# Driver.net
KiCad netlist of a schematic drawn in Altium Designer
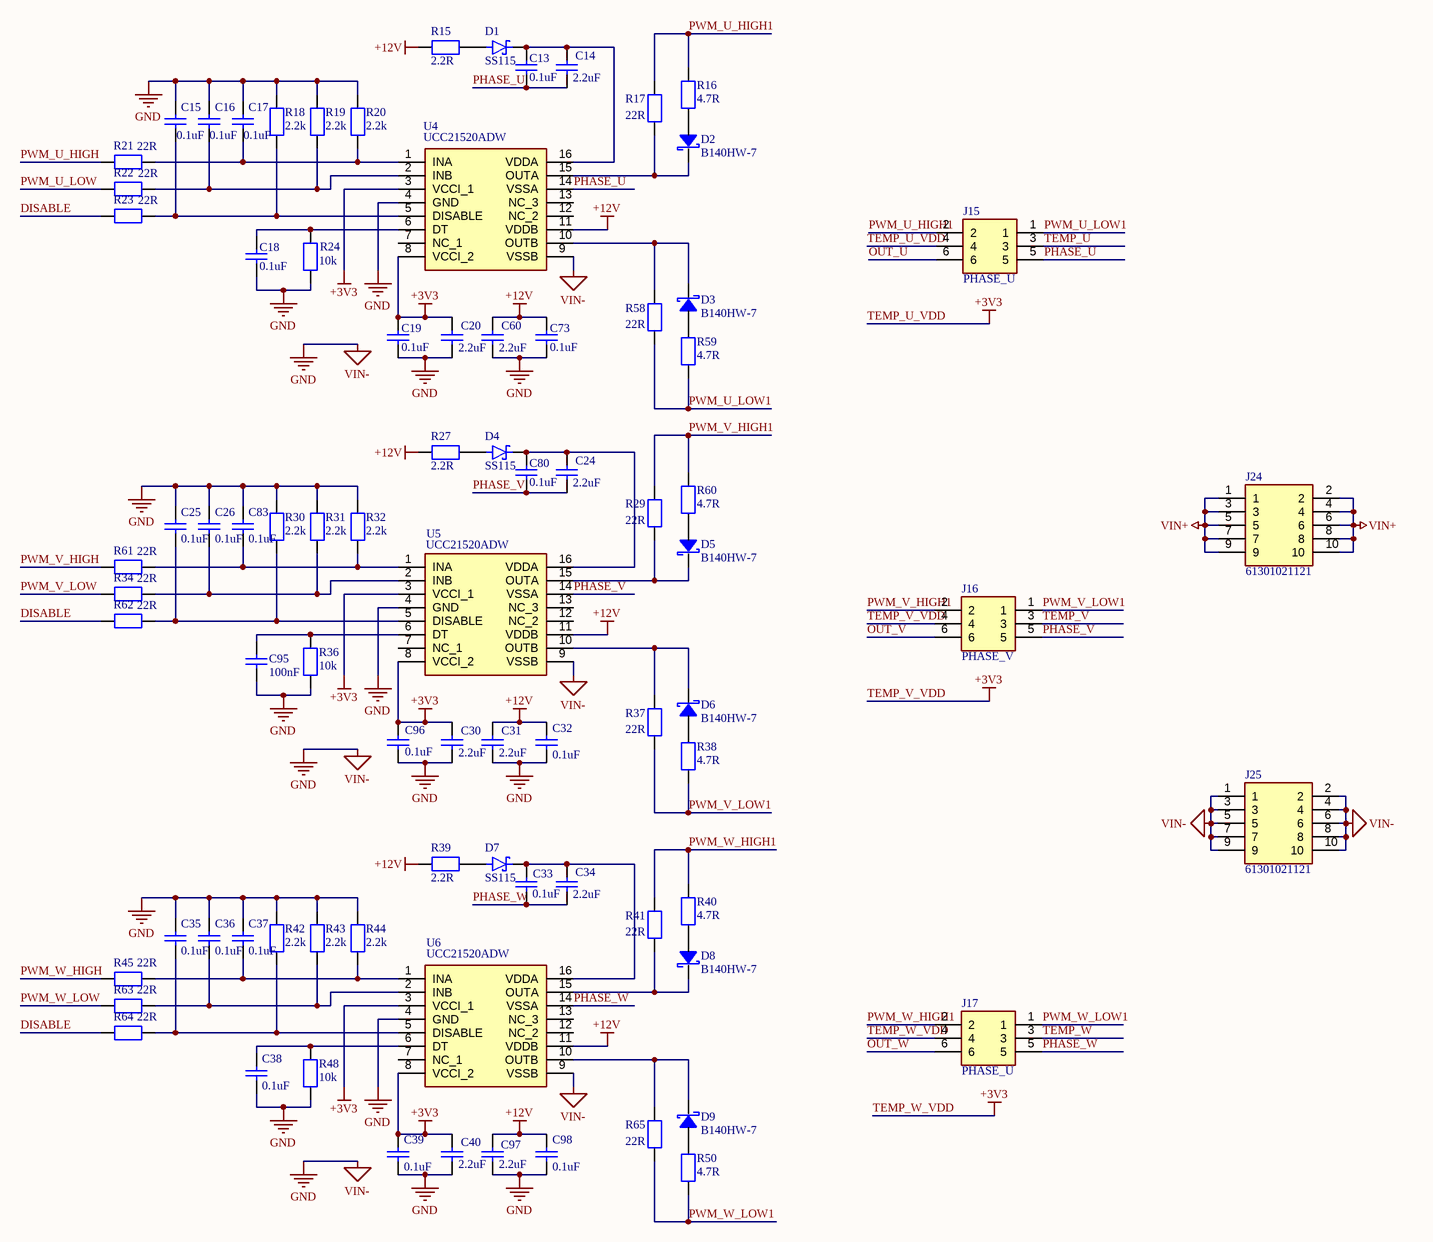
[diagram p0: Driver.SchDoc]

(export (version "E")
  (design (tool "Eeschema 10.0.6"))
  (components
    (comp (ref "C13")
      (value "0.1uF")
      (footprint "C0603")
      (description "Multilayer Ceramic Capacitors MLCC - SMD/SMT 50 V 0.1uF X7R 0603 10%")
      (fields
        (field (name "MANUFACTURER") "Yageo")
        (field (name "MANUFACTURER PART NUMBER") "CC0603KRX7R9BB104")
      )
      (libsource (lib "VESC_MotorController") (part "Cap 100nF ± 10% 50V"))
    )
    (comp (ref "C14")
      (value "2.2uF")
      (footprint "C0805")
      (description "Multilayer Ceramic Capacitors MLCC - SMD/SMT 50 V 2.2uF X7R 0805 10%")
      (fields
        (field (name "MANUFACTURER") "Yageo")
        (field (name "MANUFACTURER PART NUMBER") "CC0805KKX7R9BB225")
      )
      (libsource (lib "VESC_MotorController") (part "Cap 2.2uF ± 10% 50V"))
    )
    (comp (ref "C15")
      (value "0.1uF")
      (footprint "C0603")
      (description "Multilayer Ceramic Capacitors MLCC - SMD/SMT 50 V 0.1uF X7R 0603 10%")
      (fields
        (field (name "MANUFACTURER") "Yageo")
        (field (name "MANUFACTURER PART NUMBER") "CC0603KRX7R9BB104")
      )
      (libsource (lib "VESC_MotorController") (part "Cap 100nF ± 10% 50V"))
    )
    (comp (ref "C16")
      (value "0.1uF")
      (footprint "C0603")
      (description "Multilayer Ceramic Capacitors MLCC - SMD/SMT 50 V 0.1uF X7R 0603 10%")
      (fields
        (field (name "MANUFACTURER") "Yageo")
        (field (name "MANUFACTURER PART NUMBER") "CC0603KRX7R9BB104")
      )
      (libsource (lib "VESC_MotorController") (part "Cap 100nF ± 10% 50V"))
    )
    (comp (ref "C17")
      (value "0.1uF")
      (footprint "C0603")
      (description "Multilayer Ceramic Capacitors MLCC - SMD/SMT 50 V 0.1uF X7R 0603 10%")
      (fields
        (field (name "MANUFACTURER") "Yageo")
        (field (name "MANUFACTURER PART NUMBER") "CC0603KRX7R9BB104")
      )
      (libsource (lib "VESC_MotorController") (part "Cap 100nF ± 10% 50V"))
    )
    (comp (ref "C18")
      (value "0.1uF")
      (footprint "C0603")
      (description "Multilayer Ceramic Capacitors MLCC - SMD/SMT 50 V 0.1uF X7R 0603 10%")
      (fields
        (field (name "MANUFACTURER") "Yageo")
        (field (name "MANUFACTURER PART NUMBER") "CC0603KRX7R9BB104")
      )
      (libsource (lib "VESC_MotorController") (part "Cap 100nF ± 10% 50V"))
    )
    (comp (ref "C19")
      (value "0.1uF")
      (footprint "C0603")
      (description "Multilayer Ceramic Capacitors MLCC - SMD/SMT 50 V 0.1uF X7R 0603 10%")
      (fields
        (field (name "MANUFACTURER") "Yageo")
        (field (name "MANUFACTURER PART NUMBER") "CC0603KRX7R9BB104")
      )
      (libsource (lib "VESC_MotorController") (part "Cap 100nF ± 10% 50V"))
    )
    (comp (ref "C20")
      (value "2.2uF")
      (footprint "C0805")
      (description "Multilayer Ceramic Capacitors MLCC - SMD/SMT 50 V 2.2uF X7R 0805 10%")
      (fields
        (field (name "MANUFACTURER") "Yageo")
        (field (name "MANUFACTURER PART NUMBER") "CC0805KKX7R9BB225")
      )
      (libsource (lib "VESC_MotorController") (part "Cap 2.2uF ± 10% 50V"))
    )
    (comp (ref "C24")
      (value "2.2uF")
      (footprint "C0805")
      (description "Multilayer Ceramic Capacitors MLCC - SMD/SMT 50 V 2.2uF X7R 0805 10%")
      (fields
        (field (name "MANUFACTURER") "Yageo")
        (field (name "MANUFACTURER PART NUMBER") "CC0805KKX7R9BB225")
      )
      (libsource (lib "VESC_MotorController") (part "Cap 2.2uF ± 10% 50V"))
    )
    (comp (ref "C25")
      (value "0.1uF")
      (footprint "C0603")
      (description "Multilayer Ceramic Capacitors MLCC - SMD/SMT 50 V 0.1uF X7R 0603 10%")
      (fields
        (field (name "MANUFACTURER") "Yageo")
        (field (name "MANUFACTURER PART NUMBER") "CC0603KRX7R9BB104")
      )
      (libsource (lib "VESC_MotorController") (part "Cap 100nF ± 10% 50V"))
    )
    (comp (ref "C26")
      (value "0.1uF")
      (footprint "C0603")
      (description "Multilayer Ceramic Capacitors MLCC - SMD/SMT 50 V 0.1uF X7R 0603 10%")
      (fields
        (field (name "MANUFACTURER") "Yageo")
        (field (name "MANUFACTURER PART NUMBER") "CC0603KRX7R9BB104")
      )
      (libsource (lib "VESC_MotorController") (part "Cap 100nF ± 10% 50V"))
    )
    (comp (ref "C30")
      (value "2.2uF")
      (footprint "C0805")
      (description "Multilayer Ceramic Capacitors MLCC - SMD/SMT 50 V 2.2uF X7R 0805 10%")
      (fields
        (field (name "MANUFACTURER") "Yageo")
        (field (name "MANUFACTURER PART NUMBER") "CC0805KKX7R9BB225")
      )
      (libsource (lib "VESC_MotorController") (part "Cap 2.2uF ± 10% 50V"))
    )
    (comp (ref "C31")
      (value "2.2uF")
      (footprint "C0805")
      (description "Multilayer Ceramic Capacitors MLCC - SMD/SMT 50 V 2.2uF X7R 0805 10%")
      (fields
        (field (name "MANUFACTURER") "Yageo")
        (field (name "MANUFACTURER PART NUMBER") "CC0805KKX7R9BB225")
      )
      (libsource (lib "VESC_MotorController") (part "Cap 2.2uF ± 10% 50V"))
    )
    (comp (ref "C32")
      (value "0.1uF")
      (footprint "C0603")
      (description "Multilayer Ceramic Capacitors MLCC - SMD/SMT 50 V 0.1uF X7R 0603 10%")
      (fields
        (field (name "MANUFACTURER") "Yageo")
        (field (name "MANUFACTURER PART NUMBER") "CC0603KRX7R9BB104")
      )
      (libsource (lib "VESC_MotorController") (part "Cap 100nF ± 10% 50V"))
    )
    (comp (ref "C33")
      (value "0.1uF")
      (footprint "C0603")
      (description "Multilayer Ceramic Capacitors MLCC - SMD/SMT 50 V 0.1uF X7R 0603 10%")
      (fields
        (field (name "MANUFACTURER") "Yageo")
        (field (name "MANUFACTURER PART NUMBER") "CC0603KRX7R9BB104")
      )
      (libsource (lib "VESC_MotorController") (part "Cap 100nF ± 10% 50V"))
    )
    (comp (ref "C34")
      (value "2.2uF")
      (footprint "C0805")
      (description "Multilayer Ceramic Capacitors MLCC - SMD/SMT 50 V 2.2uF X7R 0805 10%")
      (fields
        (field (name "MANUFACTURER") "Yageo")
        (field (name "MANUFACTURER PART NUMBER") "CC0805KKX7R9BB225")
      )
      (libsource (lib "VESC_MotorController") (part "Cap 2.2uF ± 10% 50V"))
    )
    (comp (ref "C35")
      (value "0.1uF")
      (footprint "C0603")
      (description "Multilayer Ceramic Capacitors MLCC - SMD/SMT 50 V 0.1uF X7R 0603 10%")
      (fields
        (field (name "MANUFACTURER") "Yageo")
        (field (name "MANUFACTURER PART NUMBER") "CC0603KRX7R9BB104")
      )
      (libsource (lib "VESC_MotorController") (part "Cap 100nF ± 10% 50V"))
    )
    (comp (ref "C36")
      (value "0.1uF")
      (footprint "C0603")
      (description "Multilayer Ceramic Capacitors MLCC - SMD/SMT 50 V 0.1uF X7R 0603 10%")
      (fields
        (field (name "MANUFACTURER") "Yageo")
        (field (name "MANUFACTURER PART NUMBER") "CC0603KRX7R9BB104")
      )
      (libsource (lib "VESC_MotorController") (part "Cap 100nF ± 10% 50V"))
    )
    (comp (ref "C37")
      (value "0.1uF")
      (footprint "C0603")
      (description "Multilayer Ceramic Capacitors MLCC - SMD/SMT 50 V 0.1uF X7R 0603 10%")
      (fields
        (field (name "MANUFACTURER") "Yageo")
        (field (name "MANUFACTURER PART NUMBER") "CC0603KRX7R9BB104")
      )
      (libsource (lib "VESC_MotorController") (part "Cap 100nF ± 10% 50V"))
    )
    (comp (ref "C38")
      (value "0.1uF")
      (footprint "C0603")
      (description "Multilayer Ceramic Capacitors MLCC - SMD/SMT 50 V 0.1uF X7R 0603 10%")
      (fields
        (field (name "MANUFACTURER") "Yageo")
        (field (name "MANUFACTURER PART NUMBER") "CC0603KRX7R9BB104")
      )
      (libsource (lib "VESC_MotorController") (part "Cap 100nF ± 10% 50V"))
    )
    (comp (ref "C39")
      (value "0.1uF")
      (footprint "C0603")
      (description "Multilayer Ceramic Capacitors MLCC - SMD/SMT 50 V 0.1uF X7R 0603 10%")
      (fields
        (field (name "MANUFACTURER") "Yageo")
        (field (name "MANUFACTURER PART NUMBER") "CC0603KRX7R9BB104")
      )
      (libsource (lib "VESC_MotorController") (part "Cap 100nF ± 10% 50V"))
    )
    (comp (ref "C40")
      (value "2.2uF")
      (footprint "C0805")
      (description "Multilayer Ceramic Capacitors MLCC - SMD/SMT 50 V 2.2uF X7R 0805 10%")
      (fields
        (field (name "MANUFACTURER") "Yageo")
        (field (name "MANUFACTURER PART NUMBER") "CC0805KKX7R9BB225")
      )
      (libsource (lib "VESC_MotorController") (part "Cap 2.2uF ± 10% 50V"))
    )
    (comp (ref "C60")
      (value "2.2uF")
      (footprint "C0805")
      (description "Multilayer Ceramic Capacitors MLCC - SMD/SMT 50 V 2.2uF X7R 0805 10%")
      (fields
        (field (name "MANUFACTURER") "Yageo")
        (field (name "MANUFACTURER PART NUMBER") "CC0805KKX7R9BB225")
      )
      (libsource (lib "VESC_MotorController") (part "Cap 2.2uF ± 10% 50V"))
    )
    (comp (ref "C73")
      (value "0.1uF")
      (footprint "C0603")
      (description "Multilayer Ceramic Capacitors MLCC - SMD/SMT 50 V 0.1uF X7R 0603 10%")
      (fields
        (field (name "MANUFACTURER") "Yageo")
        (field (name "MANUFACTURER PART NUMBER") "CC0603KRX7R9BB104")
      )
      (libsource (lib "VESC_MotorController") (part "Cap 100nF ± 10% 50V"))
    )
    (comp (ref "C80")
      (value "0.1uF")
      (footprint "C0603")
      (description "Multilayer Ceramic Capacitors MLCC - SMD/SMT 50 V 0.1uF X7R 0603 10%")
      (fields
        (field (name "MANUFACTURER") "Yageo")
        (field (name "MANUFACTURER PART NUMBER") "CC0603KRX7R9BB104")
      )
      (libsource (lib "VESC_MotorController") (part "Cap 100nF ± 10% 50V"))
    )
    (comp (ref "C83")
      (value "0.1uF")
      (footprint "C0603")
      (description "Multilayer Ceramic Capacitors MLCC - SMD/SMT 50 V 0.1uF X7R 0603 10%")
      (fields
        (field (name "MANUFACTURER") "Yageo")
        (field (name "MANUFACTURER PART NUMBER") "CC0603KRX7R9BB104")
      )
      (libsource (lib "VESC_MotorController") (part "Cap 100nF ± 10% 50V"))
    )
    (comp (ref "C95")
      (value "100nF")
      (footprint "C0603")
      (description "100nF ± 10% 50V")
      (fields
        (field (name "MANUFACTURER") "Yageo")
        (field (name "MANUFACTURER PART NUMBER") "CS0603KRX7R9BB104")
      )
      (libsource (lib "VESC_MotorController") (part "100nF ± 10% 50V"))
    )
    (comp (ref "C96")
      (value "0.1uF")
      (footprint "C0603")
      (description "Multilayer Ceramic Capacitors MLCC - SMD/SMT 50 V 0.1uF X7R 0603 10%")
      (fields
        (field (name "MANUFACTURER") "Yageo")
        (field (name "MANUFACTURER PART NUMBER") "CC0603KRX7R9BB104")
      )
      (libsource (lib "VESC_MotorController") (part "Cap 100nF ± 10% 50V"))
    )
    (comp (ref "C97")
      (value "2.2uF")
      (footprint "C0805")
      (description "Multilayer Ceramic Capacitors MLCC - SMD/SMT 50 V 2.2uF X7R 0805 10%")
      (fields
        (field (name "MANUFACTURER") "Yageo")
        (field (name "MANUFACTURER PART NUMBER") "CC0805KKX7R9BB225")
      )
      (libsource (lib "VESC_MotorController") (part "Cap 2.2uF ± 10% 50V"))
    )
    (comp (ref "C98")
      (value "0.1uF")
      (footprint "C0603")
      (description "Multilayer Ceramic Capacitors MLCC - SMD/SMT 50 V 0.1uF X7R 0603 10%")
      (fields
        (field (name "MANUFACTURER") "Yageo")
        (field (name "MANUFACTURER PART NUMBER") "CC0603KRX7R9BB104")
      )
      (libsource (lib "VESC_MotorController") (part "Cap 100nF ± 10% 50V"))
    )
    (comp (ref "D1")
      (value "SS115")
      (footprint "DIOM4325X250N")
      (description "Schottky Diodes & Rectifiers 1A, 150V, Schottky Rectifier")
      (fields (field (name "MANUFACTURER") "Taiwan Semiconductor"))
      (libsource (lib "VESC_MotorController") (part "S Diodes & Rectifiers 1A 150V"))
    )
    (comp (ref "D2")
      (value "B140HW-7")
      (footprint "SOD123")
      (description "Schottky Diodes & Rectifiers SCHOTTKY RECTIFIER SOD-123 1.0A 40V")
      (fields (field (name "MANUFACTURER") "Diodes"))
      (libsource (lib "VESC_MotorController") (part "S Diodes & Rectifiers 1A 40V"))
    )
    (comp (ref "D3")
      (value "B140HW-7")
      (footprint "SOD123")
      (description "Schottky Diodes & Rectifiers SCHOTTKY RECTIFIER SOD-123 1.0A 40V")
      (fields (field (name "MANUFACTURER") "Diodes"))
      (libsource (lib "VESC_MotorController") (part "S Diodes & Rectifiers 1A 40V"))
    )
    (comp (ref "D4")
      (value "SS115")
      (footprint "DIOM4325X250N")
      (description "Schottky Diodes & Rectifiers 1A, 150V, Schottky Rectifier")
      (fields (field (name "MANUFACTURER") "Taiwan Semiconductor"))
      (libsource (lib "VESC_MotorController") (part "S Diodes & Rectifiers 1A 150V"))
    )
    (comp (ref "D5")
      (value "B140HW-7")
      (footprint "SOD123")
      (description "Schottky Diodes & Rectifiers SCHOTTKY RECTIFIER SOD-123 1.0A 40V")
      (fields (field (name "MANUFACTURER") "Diodes"))
      (libsource (lib "VESC_MotorController") (part "S Diodes & Rectifiers 1A 40V"))
    )
    (comp (ref "D6")
      (value "B140HW-7")
      (footprint "SOD123")
      (description "Schottky Diodes & Rectifiers SCHOTTKY RECTIFIER SOD-123 1.0A 40V")
      (fields (field (name "MANUFACTURER") "Diodes"))
      (libsource (lib "VESC_MotorController") (part "S Diodes & Rectifiers 1A 40V"))
    )
    (comp (ref "D7")
      (value "SS115")
      (footprint "DIOM4325X250N")
      (description "Schottky Diodes & Rectifiers 1A, 150V, Schottky Rectifier")
      (fields (field (name "MANUFACTURER") "Taiwan Semiconductor"))
      (libsource (lib "VESC_MotorController") (part "S Diodes & Rectifiers 1A 150V"))
    )
    (comp (ref "D8")
      (value "B140HW-7")
      (footprint "SOD123")
      (description "Schottky Diodes & Rectifiers SCHOTTKY RECTIFIER SOD-123 1.0A 40V")
      (fields (field (name "MANUFACTURER") "Diodes"))
      (libsource (lib "VESC_MotorController") (part "S Diodes & Rectifiers 1A 40V"))
    )
    (comp (ref "D9")
      (value "B140HW-7")
      (footprint "SOD123")
      (description "Schottky Diodes & Rectifiers SCHOTTKY RECTIFIER SOD-123 1.0A 40V")
      (fields (field (name "MANUFACTURER") "Diodes"))
      (libsource (lib "VESC_MotorController") (part "S Diodes & Rectifiers 1A 40V"))
    )
    (comp (ref "J15")
      (value "PHASE_U")
      (footprint "61300621121")
      (fields
        (field (name "MANUFACTURER") "Wurth Elektronik")
        (field (name "MANUFACTURER PART NUMBER") "61300621121")
      )
      (libsource (lib "VESC_MotorController") (part "Header 6 Pin_2"))
    )
    (comp (ref "J16")
      (value "PHASE_V")
      (footprint "61300621121")
      (fields
        (field (name "MANUFACTURER") "Wurth Elektronik")
        (field (name "MANUFACTURER PART NUMBER") "61300621121")
      )
      (libsource (lib "VESC_MotorController") (part "Header 6 Pin_2"))
    )
    (comp (ref "J17")
      (value "PHASE_U")
      (footprint "61300621121")
      (fields
        (field (name "MANUFACTURER") "Wurth Elektronik")
        (field (name "MANUFACTURER PART NUMBER") "61300621121")
      )
      (libsource (lib "VESC_MotorController") (part "Header 6 Pin_2"))
    )
    (comp (ref "J24")
      (value "61301021121")
      (footprint "HDRV10W64P254X254_2X5_1270X508X869P")
      (description "Wurth Elektronik WR-PHD, 10 Way, 2 Row, Straight Pin Header")
      (fields (field (name "MANUFACTURER") "Wurth Elektronik"))
      (libsource (lib "61301021121") (part "61301021121"))
    )
    (comp (ref "J25")
      (value "61301021121")
      (footprint "HDRV10W64P254X254_2X5_1270X508X869P")
      (description "Wurth Elektronik WR-PHD, 10 Way, 2 Row, Straight Pin Header")
      (fields (field (name "MANUFACTURER") "Wurth Elektronik"))
      (libsource (lib "61301021121") (part "61301021121"))
    )
    (comp (ref "R15")
      (value "2.2R")
      (footprint "R0603")
      (description "Thick Film Resistors - SMD 2.2 Ohms 100mW 0603 1%")
      (fields
        (field (name "MANUFACTURER PART NUMBER") "RC0603FR-072R2L")
        (field (name "MANUFACTURER") "Yageo")
      )
      (libsource (lib "VESC_MotorController") (part "Res 2.2ohm ±1% 0.1W"))
    )
    (comp (ref "R16")
      (value "4.7R")
      (footprint "R0603")
      (description "Thick Film Resistors - SMD 4.7 Ohms 100mW 0603 1%")
      (fields
        (field (name "MANUFACTURER PART NUMBER") "RC0603FR-074R7L")
        (field (name "MANUFACTURER") "Yageo")
      )
      (libsource (lib "VESC_MotorController") (part "Res 4.7ohm ±1% 0.1W"))
    )
    (comp (ref "R17")
      (value "22R")
      (footprint "R0603")
      (description "Thick Film Resistors - SMD 22 Ohms 100mW 0603 1%")
      (fields
        (field (name "MANUFACTURER PART NUMBER") "RC0603FR-0722RL")
        (field (name "MANUFACTURER") "Yageo")
      )
      (libsource (lib "VESC_MotorController") (part "Res 22ohm ±1% 0.1W"))
    )
    (comp (ref "R18")
      (value "2.2k")
      (footprint "R0603")
      (description "2.2 kOhms ±1% 0.1W")
      (fields
        (field (name "MANUFACTURER") "Yageo")
        (field (name "MANUFACTURER PART NUMBER") "RC0603FR-072K2L")
      )
      (libsource (lib "VESC_MotorController") (part "2.2 kOhms ±1% 0.1W"))
    )
    (comp (ref "R19")
      (value "2.2k")
      (footprint "R0603")
      (description "2.2 kOhms ±1% 0.1W")
      (fields
        (field (name "MANUFACTURER") "Yageo")
        (field (name "MANUFACTURER PART NUMBER") "RC0603FR-072K2L")
      )
      (libsource (lib "VESC_MotorController") (part "2.2 kOhms ±1% 0.1W"))
    )
    (comp (ref "R20")
      (value "2.2k")
      (footprint "R0603")
      (description "2.2 kOhms ±1% 0.1W")
      (fields
        (field (name "MANUFACTURER") "Yageo")
        (field (name "MANUFACTURER PART NUMBER") "RC0603FR-072K2L")
      )
      (libsource (lib "VESC_MotorController") (part "2.2 kOhms ±1% 0.1W"))
    )
    (comp (ref "R21")
      (value "22R")
      (footprint "R0603")
      (description "Thick Film Resistors - SMD 22 Ohms 100mW 0603 1%")
      (fields
        (field (name "MANUFACTURER PART NUMBER") "RC0603FR-0722RL")
        (field (name "MANUFACTURER") "Yageo")
      )
      (libsource (lib "VESC_MotorController") (part "Res 22ohm ±1% 0.1W"))
    )
    (comp (ref "R22")
      (value "22R")
      (footprint "R0603")
      (description "Thick Film Resistors - SMD 22 Ohms 100mW 0603 1%")
      (fields
        (field (name "MANUFACTURER PART NUMBER") "RC0603FR-0722RL")
        (field (name "MANUFACTURER") "Yageo")
      )
      (libsource (lib "VESC_MotorController") (part "Res 22ohm ±1% 0.1W"))
    )
    (comp (ref "R23")
      (value "22R")
      (footprint "R0603")
      (description "Thick Film Resistors - SMD 22 Ohms 100mW 0603 1%")
      (fields
        (field (name "MANUFACTURER PART NUMBER") "RC0603FR-0722RL")
        (field (name "MANUFACTURER") "Yageo")
      )
      (libsource (lib "VESC_MotorController") (part "Res 22ohm ±1% 0.1W"))
    )
    (comp (ref "R24")
      (value "10k")
      (footprint "R0603")
      (description "10 kOhms ±1% 0.1W")
      (fields
        (field (name "MANUFACTURER") "Yageo")
        (field (name "MANUFACTURER PART NUMBER") "RC0603FR-0710KL")
      )
      (libsource (lib "VESC_MotorController") (part "10 kOhms ±1% 0.1W"))
    )
    (comp (ref "R27")
      (value "2.2R")
      (footprint "R0603")
      (description "Thick Film Resistors - SMD 2.2 Ohms 100mW 0603 1%")
      (fields
        (field (name "MANUFACTURER PART NUMBER") "RC0603FR-072R2L")
        (field (name "MANUFACTURER") "Yageo")
      )
      (libsource (lib "VESC_MotorController") (part "Res 2.2ohm ±1% 0.1W"))
    )
    (comp (ref "R29")
      (value "22R")
      (footprint "R0603")
      (description "Thick Film Resistors - SMD 22 Ohms 100mW 0603 1%")
      (fields
        (field (name "MANUFACTURER PART NUMBER") "RC0603FR-0722RL")
        (field (name "MANUFACTURER") "Yageo")
      )
      (libsource (lib "VESC_MotorController") (part "Res 22ohm ±1% 0.1W"))
    )
    (comp (ref "R30")
      (value "2.2k")
      (footprint "R0603")
      (description "2.2 kOhms ±1% 0.1W")
      (fields
        (field (name "MANUFACTURER") "Yageo")
        (field (name "MANUFACTURER PART NUMBER") "RC0603FR-072K2L")
      )
      (libsource (lib "VESC_MotorController") (part "2.2 kOhms ±1% 0.1W"))
    )
    (comp (ref "R31")
      (value "2.2k")
      (footprint "R0603")
      (description "2.2 kOhms ±1% 0.1W")
      (fields
        (field (name "MANUFACTURER") "Yageo")
        (field (name "MANUFACTURER PART NUMBER") "RC0603FR-072K2L")
      )
      (libsource (lib "VESC_MotorController") (part "2.2 kOhms ±1% 0.1W"))
    )
    (comp (ref "R32")
      (value "2.2k")
      (footprint "R0603")
      (description "2.2 kOhms ±1% 0.1W")
      (fields
        (field (name "MANUFACTURER") "Yageo")
        (field (name "MANUFACTURER PART NUMBER") "RC0603FR-072K2L")
      )
      (libsource (lib "VESC_MotorController") (part "2.2 kOhms ±1% 0.1W"))
    )
    (comp (ref "R34")
      (value "22R")
      (footprint "R0603")
      (description "Thick Film Resistors - SMD 22 Ohms 100mW 0603 1%")
      (fields
        (field (name "MANUFACTURER PART NUMBER") "RC0603FR-0722RL")
        (field (name "MANUFACTURER") "Yageo")
      )
      (libsource (lib "VESC_MotorController") (part "Res 22ohm ±1% 0.1W"))
    )
    (comp (ref "R36")
      (value "10k")
      (footprint "R0603")
      (description "10 kOhms ±1% 0.1W")
      (fields
        (field (name "MANUFACTURER") "Yageo")
        (field (name "MANUFACTURER PART NUMBER") "RC0603FR-0710KL")
      )
      (libsource (lib "VESC_MotorController") (part "10 kOhms ±1% 0.1W"))
    )
    (comp (ref "R37")
      (value "22R")
      (footprint "R0603")
      (description "Thick Film Resistors - SMD 22 Ohms 100mW 0603 1%")
      (fields
        (field (name "MANUFACTURER PART NUMBER") "RC0603FR-0722RL")
        (field (name "MANUFACTURER") "Yageo")
      )
      (libsource (lib "VESC_MotorController") (part "Res 22ohm ±1% 0.1W"))
    )
    (comp (ref "R38")
      (value "4.7R")
      (footprint "R0603")
      (description "Thick Film Resistors - SMD 4.7 Ohms 100mW 0603 1%")
      (fields
        (field (name "MANUFACTURER PART NUMBER") "RC0603FR-074R7L")
        (field (name "MANUFACTURER") "Yageo")
      )
      (libsource (lib "VESC_MotorController") (part "Res 4.7ohm ±1% 0.1W"))
    )
    (comp (ref "R39")
      (value "2.2R")
      (footprint "R0603")
      (description "Thick Film Resistors - SMD 2.2 Ohms 100mW 0603 1%")
      (fields
        (field (name "MANUFACTURER PART NUMBER") "RC0603FR-072R2L")
        (field (name "MANUFACTURER") "Yageo")
      )
      (libsource (lib "VESC_MotorController") (part "Res 2.2ohm ±1% 0.1W"))
    )
    (comp (ref "R40")
      (value "4.7R")
      (footprint "R0603")
      (description "Thick Film Resistors - SMD 4.7 Ohms 100mW 0603 1%")
      (fields
        (field (name "MANUFACTURER PART NUMBER") "RC0603FR-074R7L")
        (field (name "MANUFACTURER") "Yageo")
      )
      (libsource (lib "VESC_MotorController") (part "Res 4.7ohm ±1% 0.1W"))
    )
    (comp (ref "R41")
      (value "22R")
      (footprint "R0603")
      (description "Thick Film Resistors - SMD 22 Ohms 100mW 0603 1%")
      (fields
        (field (name "MANUFACTURER PART NUMBER") "RC0603FR-0722RL")
        (field (name "MANUFACTURER") "Yageo")
      )
      (libsource (lib "VESC_MotorController") (part "Res 22ohm ±1% 0.1W"))
    )
    (comp (ref "R42")
      (value "2.2k")
      (footprint "R0603")
      (description "2.2 kOhms ±1% 0.1W")
      (fields
        (field (name "MANUFACTURER") "Yageo")
        (field (name "MANUFACTURER PART NUMBER") "RC0603FR-072K2L")
      )
      (libsource (lib "VESC_MotorController") (part "2.2 kOhms ±1% 0.1W"))
    )
    (comp (ref "R43")
      (value "2.2k")
      (footprint "R0603")
      (description "2.2 kOhms ±1% 0.1W")
      (fields
        (field (name "MANUFACTURER") "Yageo")
        (field (name "MANUFACTURER PART NUMBER") "RC0603FR-072K2L")
      )
      (libsource (lib "VESC_MotorController") (part "2.2 kOhms ±1% 0.1W"))
    )
    (comp (ref "R44")
      (value "2.2k")
      (footprint "R0603")
      (description "2.2 kOhms ±1% 0.1W")
      (fields
        (field (name "MANUFACTURER") "Yageo")
        (field (name "MANUFACTURER PART NUMBER") "RC0603FR-072K2L")
      )
      (libsource (lib "VESC_MotorController") (part "2.2 kOhms ±1% 0.1W"))
    )
    (comp (ref "R45")
      (value "22R")
      (footprint "R0603")
      (description "Thick Film Resistors - SMD 22 Ohms 100mW 0603 1%")
      (fields
        (field (name "MANUFACTURER PART NUMBER") "RC0603FR-0722RL")
        (field (name "MANUFACTURER") "Yageo")
      )
      (libsource (lib "VESC_MotorController") (part "Res 22ohm ±1% 0.1W"))
    )
    (comp (ref "R48")
      (value "10k")
      (footprint "R0603")
      (description "10 kOhms ±1% 0.1W")
      (fields
        (field (name "MANUFACTURER") "Yageo")
        (field (name "MANUFACTURER PART NUMBER") "RC0603FR-0710KL")
      )
      (libsource (lib "VESC_MotorController") (part "10 kOhms ±1% 0.1W"))
    )
    (comp (ref "R50")
      (value "4.7R")
      (footprint "R0603")
      (description "Thick Film Resistors - SMD 4.7 Ohms 100mW 0603 1%")
      (fields
        (field (name "MANUFACTURER PART NUMBER") "RC0603FR-074R7L")
        (field (name "MANUFACTURER") "Yageo")
      )
      (libsource (lib "VESC_MotorController") (part "Res 4.7ohm ±1% 0.1W"))
    )
    (comp (ref "R58")
      (value "22R")
      (footprint "R0603")
      (description "Thick Film Resistors - SMD 22 Ohms 100mW 0603 1%")
      (fields
        (field (name "MANUFACTURER PART NUMBER") "RC0603FR-0722RL")
        (field (name "MANUFACTURER") "Yageo")
      )
      (libsource (lib "VESC_MotorController") (part "Res 22ohm ±1% 0.1W"))
    )
    (comp (ref "R59")
      (value "4.7R")
      (footprint "R0603")
      (description "Thick Film Resistors - SMD 4.7 Ohms 100mW 0603 1%")
      (fields
        (field (name "MANUFACTURER PART NUMBER") "RC0603FR-074R7L")
        (field (name "MANUFACTURER") "Yageo")
      )
      (libsource (lib "VESC_MotorController") (part "Res 4.7ohm ±1% 0.1W"))
    )
    (comp (ref "R60")
      (value "4.7R")
      (footprint "R0603")
      (description "Thick Film Resistors - SMD 4.7 Ohms 100mW 0603 1%")
      (fields
        (field (name "MANUFACTURER PART NUMBER") "RC0603FR-074R7L")
        (field (name "MANUFACTURER") "Yageo")
      )
      (libsource (lib "VESC_MotorController") (part "Res 4.7ohm ±1% 0.1W"))
    )
    (comp (ref "R61")
      (value "22R")
      (footprint "R0603")
      (description "Thick Film Resistors - SMD 22 Ohms 100mW 0603 1%")
      (fields
        (field (name "MANUFACTURER PART NUMBER") "RC0603FR-0722RL")
        (field (name "MANUFACTURER") "Yageo")
      )
      (libsource (lib "VESC_MotorController") (part "Res 22ohm ±1% 0.1W"))
    )
    (comp (ref "R62")
      (value "22R")
      (footprint "R0603")
      (description "Thick Film Resistors - SMD 22 Ohms 100mW 0603 1%")
      (fields
        (field (name "MANUFACTURER PART NUMBER") "RC0603FR-0722RL")
        (field (name "MANUFACTURER") "Yageo")
      )
      (libsource (lib "VESC_MotorController") (part "Res 22ohm ±1% 0.1W"))
    )
    (comp (ref "R63")
      (value "22R")
      (footprint "R0603")
      (description "Thick Film Resistors - SMD 22 Ohms 100mW 0603 1%")
      (fields
        (field (name "MANUFACTURER PART NUMBER") "RC0603FR-0722RL")
        (field (name "MANUFACTURER") "Yageo")
      )
      (libsource (lib "VESC_MotorController") (part "Res 22ohm ±1% 0.1W"))
    )
    (comp (ref "R64")
      (value "22R")
      (footprint "R0603")
      (description "Thick Film Resistors - SMD 22 Ohms 100mW 0603 1%")
      (fields
        (field (name "MANUFACTURER PART NUMBER") "RC0603FR-0722RL")
        (field (name "MANUFACTURER") "Yageo")
      )
      (libsource (lib "VESC_MotorController") (part "Res 22ohm ±1% 0.1W"))
    )
    (comp (ref "R65")
      (value "22R")
      (footprint "R0603")
      (description "Thick Film Resistors - SMD 22 Ohms 100mW 0603 1%")
      (fields
        (field (name "MANUFACTURER PART NUMBER") "RC0603FR-0722RL")
        (field (name "MANUFACTURER") "Yageo")
      )
      (libsource (lib "VESC_MotorController") (part "Res 22ohm ±1% 0.1W"))
    )
    (comp (ref "U4")
      (value "UCC21520ADW")
      (footprint "SOIC127P1030X265-16N")
      (description "4A/6A, 5.7 kVrms Isolated Dual Channel Gate Driver")
      (fields (field (name "MANUFACTURER") "Texas Instruments"))
      (libsource (lib "VESC_MotorController") (part "UCC21520ADW"))
    )
    (comp (ref "U5")
      (value "UCC21520ADW")
      (footprint "SOIC127P1030X265-16N")
      (description "4A/6A, 5.7 kVrms Isolated Dual Channel Gate Driver")
      (fields (field (name "MANUFACTURER") "Texas Instruments"))
      (libsource (lib "VESC_MotorController") (part "UCC21520ADW"))
    )
    (comp (ref "U6")
      (value "UCC21520ADW")
      (footprint "SOIC127P1030X265-16N")
      (description "4A/6A, 5.7 kVrms Isolated Dual Channel Gate Driver")
      (fields (field (name "MANUFACTURER") "Texas Instruments"))
      (libsource (lib "VESC_MotorController") (part "UCC21520ADW"))
    )
  )
  (nets
    (net (code "1") (name "+3V3") (class "Default")
      (node (ref "C19") (pin "2") (pinfunction "2_2") (pintype "passive"))
      (node (ref "C20") (pin "2") (pinfunction "2_2") (pintype "passive"))
      (node (ref "C30") (pin "2") (pinfunction "2_2") (pintype "passive"))
      (node (ref "C39") (pin "2") (pinfunction "2_2") (pintype "passive"))
      (node (ref "C40") (pin "2") (pinfunction "2_2") (pintype "passive"))
      (node (ref "C96") (pin "2") (pinfunction "2_2") (pintype "passive"))
      (node (ref "J15") (pin "4") (pinfunction "4_4") (pintype "passive"))
      (node (ref "J16") (pin "4") (pinfunction "4_4") (pintype "passive"))
      (node (ref "J17") (pin "4") (pinfunction "4_4") (pintype "passive"))
      (node (ref "U4") (pin "3") (pinfunction "VCCI_1_3") (pintype "passive"))
      (node (ref "U4") (pin "8") (pinfunction "VCCI_2_8") (pintype "passive"))
      (node (ref "U5") (pin "3") (pinfunction "VCCI_1_3") (pintype "passive"))
      (node (ref "U5") (pin "8") (pinfunction "VCCI_2_8") (pintype "passive"))
      (node (ref "U6") (pin "3") (pinfunction "VCCI_1_3") (pintype "passive"))
      (node (ref "U6") (pin "8") (pinfunction "VCCI_2_8") (pintype "passive"))
    )
    (net (code "2") (name "+12V") (class "Default")
      (node (ref "C31") (pin "2") (pinfunction "2_2") (pintype "passive"))
      (node (ref "C32") (pin "2") (pinfunction "2_2") (pintype "passive"))
      (node (ref "C60") (pin "2") (pinfunction "2_2") (pintype "passive"))
      (node (ref "C73") (pin "2") (pinfunction "2_2") (pintype "passive"))
      (node (ref "C97") (pin "2") (pinfunction "2_2") (pintype "passive"))
      (node (ref "C98") (pin "2") (pinfunction "2_2") (pintype "passive"))
      (node (ref "R15") (pin "1") (pinfunction "1_1") (pintype "passive"))
      (node (ref "R27") (pin "1") (pinfunction "1_1") (pintype "passive"))
      (node (ref "R39") (pin "1") (pinfunction "1_1") (pintype "passive"))
      (node (ref "U4") (pin "11") (pinfunction "VDDB_11") (pintype "passive"))
      (node (ref "U5") (pin "11") (pinfunction "VDDB_11") (pintype "passive"))
      (node (ref "U6") (pin "11") (pinfunction "VDDB_11") (pintype "passive"))
    )
    (net (code "3") (name "/DISABLE") (class "Default")
      (node (ref "R23") (pin "1") (pinfunction "1_1") (pintype "passive"))
      (node (ref "R62") (pin "1") (pinfunction "1_1") (pintype "passive"))
      (node (ref "R64") (pin "1") (pinfunction "1_1") (pintype "passive"))
    )
    (net (code "4") (name "/OUT_U") (class "Default")
      (node (ref "J15") (pin "6") (pinfunction "6_6") (pintype "passive"))
    )
    (net (code "5") (name "/OUT_V") (class "Default")
      (node (ref "J16") (pin "6") (pinfunction "6_6") (pintype "passive"))
    )
    (net (code "6") (name "/OUT_W") (class "Default")
      (node (ref "J17") (pin "6") (pinfunction "6_6") (pintype "passive"))
    )
    (net (code "7") (name "/PHASE_U") (class "Default")
      (node (ref "C13") (pin "1") (pinfunction "1_1") (pintype "passive"))
      (node (ref "C14") (pin "1") (pinfunction "1_1") (pintype "passive"))
      (node (ref "J15") (pin "5") (pinfunction "5_5") (pintype "passive"))
      (node (ref "U4") (pin "14") (pinfunction "VSSA_14") (pintype "passive"))
    )
    (net (code "8") (name "/PHASE_V") (class "Default")
      (node (ref "C24") (pin "1") (pinfunction "1_1") (pintype "passive"))
      (node (ref "C80") (pin "1") (pinfunction "1_1") (pintype "passive"))
      (node (ref "J16") (pin "5") (pinfunction "5_5") (pintype "passive"))
      (node (ref "U5") (pin "14") (pinfunction "VSSA_14") (pintype "passive"))
    )
    (net (code "9") (name "/PHASE_W") (class "Default")
      (node (ref "C33") (pin "1") (pinfunction "1_1") (pintype "passive"))
      (node (ref "C34") (pin "1") (pinfunction "1_1") (pintype "passive"))
      (node (ref "J17") (pin "5") (pinfunction "5_5") (pintype "passive"))
      (node (ref "U6") (pin "14") (pinfunction "VSSA_14") (pintype "passive"))
    )
    (net (code "10") (name "/PWM_U_HIGH") (class "Default")
      (node (ref "R21") (pin "1") (pinfunction "1_1") (pintype "passive"))
    )
    (net (code "11") (name "/PWM_U_HIGH1") (class "Default")
      (node (ref "J15") (pin "2") (pinfunction "2_2") (pintype "passive"))
      (node (ref "R16") (pin "2") (pinfunction "2_2") (pintype "passive"))
      (node (ref "R17") (pin "2") (pinfunction "2_2") (pintype "passive"))
    )
    (net (code "12") (name "/PWM_U_LOW") (class "Default")
      (node (ref "R22") (pin "1") (pinfunction "1_1") (pintype "passive"))
    )
    (net (code "13") (name "/PWM_U_LOW1") (class "Default")
      (node (ref "J15") (pin "1") (pinfunction "1_1") (pintype "passive"))
      (node (ref "R58") (pin "1") (pinfunction "1_1") (pintype "passive"))
      (node (ref "R59") (pin "1") (pinfunction "1_1") (pintype "passive"))
    )
    (net (code "14") (name "/PWM_V_HIGH") (class "Default")
      (node (ref "R61") (pin "1") (pinfunction "1_1") (pintype "passive"))
    )
    (net (code "15") (name "/PWM_V_HIGH1") (class "Default")
      (node (ref "J16") (pin "2") (pinfunction "2_2") (pintype "passive"))
      (node (ref "R29") (pin "2") (pinfunction "2_2") (pintype "passive"))
      (node (ref "R60") (pin "2") (pinfunction "2_2") (pintype "passive"))
    )
    (net (code "16") (name "/PWM_V_LOW") (class "Default")
      (node (ref "R34") (pin "1") (pinfunction "1_1") (pintype "passive"))
    )
    (net (code "17") (name "/PWM_V_LOW1") (class "Default")
      (node (ref "J16") (pin "1") (pinfunction "1_1") (pintype "passive"))
      (node (ref "R37") (pin "1") (pinfunction "1_1") (pintype "passive"))
      (node (ref "R38") (pin "1") (pinfunction "1_1") (pintype "passive"))
    )
    (net (code "18") (name "/PWM_W_HIGH") (class "Default")
      (node (ref "R45") (pin "1") (pinfunction "1_1") (pintype "passive"))
    )
    (net (code "19") (name "/PWM_W_HIGH1") (class "Default")
      (node (ref "J17") (pin "2") (pinfunction "2_2") (pintype "passive"))
      (node (ref "R40") (pin "2") (pinfunction "2_2") (pintype "passive"))
      (node (ref "R41") (pin "2") (pinfunction "2_2") (pintype "passive"))
    )
    (net (code "20") (name "/PWM_W_LOW") (class "Default")
      (node (ref "R63") (pin "1") (pinfunction "1_1") (pintype "passive"))
    )
    (net (code "21") (name "/PWM_W_LOW1") (class "Default")
      (node (ref "J17") (pin "1") (pinfunction "1_1") (pintype "passive"))
      (node (ref "R50") (pin "1") (pinfunction "1_1") (pintype "passive"))
      (node (ref "R65") (pin "1") (pinfunction "1_1") (pintype "passive"))
    )
    (net (code "22") (name "/TEMP_U") (class "Default")
      (node (ref "J15") (pin "3") (pinfunction "3_3") (pintype "passive"))
    )
    (net (code "23") (name "/TEMP_V") (class "Default")
      (node (ref "J16") (pin "3") (pinfunction "3_3") (pintype "passive"))
    )
    (net (code "24") (name "/TEMP_W") (class "Default")
      (node (ref "J17") (pin "3") (pinfunction "3_3") (pintype "passive"))
    )
    (net (code "25") (name "GND") (class "Default")
      (node (ref "C15") (pin "2") (pinfunction "2_2") (pintype "passive"))
      (node (ref "C16") (pin "2") (pinfunction "2_2") (pintype "passive"))
      (node (ref "C17") (pin "2") (pinfunction "2_2") (pintype "passive"))
      (node (ref "C18") (pin "1") (pinfunction "1_1") (pintype "passive"))
      (node (ref "C19") (pin "1") (pinfunction "1_1") (pintype "passive"))
      (node (ref "C20") (pin "1") (pinfunction "1_1") (pintype "passive"))
      (node (ref "C25") (pin "2") (pinfunction "2_2") (pintype "passive"))
      (node (ref "C26") (pin "2") (pinfunction "2_2") (pintype "passive"))
      (node (ref "C30") (pin "1") (pinfunction "1_1") (pintype "passive"))
      (node (ref "C31") (pin "1") (pinfunction "1_1") (pintype "passive"))
      (node (ref "C32") (pin "1") (pinfunction "1_1") (pintype "passive"))
      (node (ref "C35") (pin "2") (pinfunction "2_2") (pintype "passive"))
      (node (ref "C36") (pin "2") (pinfunction "2_2") (pintype "passive"))
      (node (ref "C37") (pin "2") (pinfunction "2_2") (pintype "passive"))
      (node (ref "C38") (pin "1") (pinfunction "1_1") (pintype "passive"))
      (node (ref "C39") (pin "1") (pinfunction "1_1") (pintype "passive"))
      (node (ref "C40") (pin "1") (pinfunction "1_1") (pintype "passive"))
      (node (ref "C60") (pin "1") (pinfunction "1_1") (pintype "passive"))
      (node (ref "C73") (pin "1") (pinfunction "1_1") (pintype "passive"))
      (node (ref "C83") (pin "2") (pinfunction "2_2") (pintype "passive"))
      (node (ref "C95") (pin "1") (pinfunction "1_1") (pintype "passive"))
      (node (ref "C96") (pin "1") (pinfunction "1_1") (pintype "passive"))
      (node (ref "C97") (pin "1") (pinfunction "1_1") (pintype "passive"))
      (node (ref "C98") (pin "1") (pinfunction "1_1") (pintype "passive"))
      (node (ref "J25") (pin "1") (pinfunction "1_1") (pintype "passive"))
      (node (ref "J25") (pin "10") (pinfunction "10_10") (pintype "passive"))
      (node (ref "J25") (pin "2") (pinfunction "2_2") (pintype "passive"))
      (node (ref "J25") (pin "3") (pinfunction "3_3") (pintype "passive"))
      (node (ref "J25") (pin "4") (pinfunction "4_4") (pintype "passive"))
      (node (ref "J25") (pin "5") (pinfunction "5_5") (pintype "passive"))
      (node (ref "J25") (pin "6") (pinfunction "6_6") (pintype "passive"))
      (node (ref "J25") (pin "7") (pinfunction "7_7") (pintype "passive"))
      (node (ref "J25") (pin "8") (pinfunction "8_8") (pintype "passive"))
      (node (ref "J25") (pin "9") (pinfunction "9_9") (pintype "passive"))
      (node (ref "R18") (pin "2") (pinfunction "2_2") (pintype "passive"))
      (node (ref "R19") (pin "2") (pinfunction "2_2") (pintype "passive"))
      (node (ref "R20") (pin "2") (pinfunction "2_2") (pintype "passive"))
      (node (ref "R24") (pin "1") (pinfunction "1_1") (pintype "passive"))
      (node (ref "R30") (pin "2") (pinfunction "2_2") (pintype "passive"))
      (node (ref "R31") (pin "2") (pinfunction "2_2") (pintype "passive"))
      (node (ref "R32") (pin "2") (pinfunction "2_2") (pintype "passive"))
      (node (ref "R36") (pin "1") (pinfunction "1_1") (pintype "passive"))
      (node (ref "R42") (pin "2") (pinfunction "2_2") (pintype "passive"))
      (node (ref "R43") (pin "2") (pinfunction "2_2") (pintype "passive"))
      (node (ref "R44") (pin "2") (pinfunction "2_2") (pintype "passive"))
      (node (ref "R48") (pin "1") (pinfunction "1_1") (pintype "passive"))
      (node (ref "U4") (pin "4") (pinfunction "GND_4") (pintype "passive"))
      (node (ref "U4") (pin "9") (pinfunction "VSSB_9") (pintype "passive"))
      (node (ref "U5") (pin "4") (pinfunction "GND_4") (pintype "passive"))
      (node (ref "U5") (pin "9") (pinfunction "VSSB_9") (pintype "passive"))
      (node (ref "U6") (pin "4") (pinfunction "GND_4") (pintype "passive"))
      (node (ref "U6") (pin "9") (pinfunction "VSSB_9") (pintype "passive"))
    )
    (net (code "26") (name "Net-(D1-K)") (class "Default")
      (node (ref "C13") (pin "2") (pinfunction "2_2") (pintype "passive"))
      (node (ref "C14") (pin "2") (pinfunction "2_2") (pintype "passive"))
      (node (ref "D1") (pin "C") (pinfunction "K_C") (pintype "passive"))
      (node (ref "U4") (pin "16") (pinfunction "VDDA_16") (pintype "passive"))
    )
    (net (code "27") (name "Net-(D1-PadA)") (class "Default")
      (node (ref "D1") (pin "A") (pinfunction "A_A") (pintype "passive"))
      (node (ref "R15") (pin "2") (pinfunction "2_2") (pintype "passive"))
    )
    (net (code "28") (name "Net-(D2-PadA)") (class "Default")
      (node (ref "D2") (pin "A") (pinfunction "A_A") (pintype "passive"))
      (node (ref "R16") (pin "1") (pinfunction "1_1") (pintype "passive"))
    )
    (net (code "29") (name "Net-(D3-PadA)") (class "Default")
      (node (ref "D3") (pin "A") (pinfunction "A_A") (pintype "passive"))
      (node (ref "R59") (pin "2") (pinfunction "2_2") (pintype "passive"))
    )
    (net (code "30") (name "Net-(D4-K)") (class "Default")
      (node (ref "C24") (pin "2") (pinfunction "2_2") (pintype "passive"))
      (node (ref "C80") (pin "2") (pinfunction "2_2") (pintype "passive"))
      (node (ref "D4") (pin "C") (pinfunction "K_C") (pintype "passive"))
      (node (ref "U5") (pin "16") (pinfunction "VDDA_16") (pintype "passive"))
    )
    (net (code "31") (name "Net-(D4-PadA)") (class "Default")
      (node (ref "D4") (pin "A") (pinfunction "A_A") (pintype "passive"))
      (node (ref "R27") (pin "2") (pinfunction "2_2") (pintype "passive"))
    )
    (net (code "32") (name "Net-(D5-PadA)") (class "Default")
      (node (ref "D5") (pin "A") (pinfunction "A_A") (pintype "passive"))
      (node (ref "R60") (pin "1") (pinfunction "1_1") (pintype "passive"))
    )
    (net (code "33") (name "Net-(D6-PadA)") (class "Default")
      (node (ref "D6") (pin "A") (pinfunction "A_A") (pintype "passive"))
      (node (ref "R38") (pin "2") (pinfunction "2_2") (pintype "passive"))
    )
    (net (code "34") (name "Net-(D7-K)") (class "Default")
      (node (ref "C33") (pin "2") (pinfunction "2_2") (pintype "passive"))
      (node (ref "C34") (pin "2") (pinfunction "2_2") (pintype "passive"))
      (node (ref "D7") (pin "C") (pinfunction "K_C") (pintype "passive"))
      (node (ref "U6") (pin "16") (pinfunction "VDDA_16") (pintype "passive"))
    )
    (net (code "35") (name "Net-(D7-PadA)") (class "Default")
      (node (ref "D7") (pin "A") (pinfunction "A_A") (pintype "passive"))
      (node (ref "R39") (pin "2") (pinfunction "2_2") (pintype "passive"))
    )
    (net (code "36") (name "Net-(D8-PadA)") (class "Default")
      (node (ref "D8") (pin "A") (pinfunction "A_A") (pintype "passive"))
      (node (ref "R40") (pin "1") (pinfunction "1_1") (pintype "passive"))
    )
    (net (code "37") (name "Net-(D9-PadA)") (class "Default")
      (node (ref "D9") (pin "A") (pinfunction "A_A") (pintype "passive"))
      (node (ref "R50") (pin "2") (pinfunction "2_2") (pintype "passive"))
    )
    (net (code "38") (name "Net-(U4-DISABLE)") (class "Default")
      (node (ref "C15") (pin "1") (pinfunction "1_1") (pintype "passive"))
      (node (ref "R18") (pin "1") (pinfunction "1_1") (pintype "passive"))
      (node (ref "R23") (pin "2") (pinfunction "2_2") (pintype "passive"))
      (node (ref "U4") (pin "5") (pinfunction "DISABLE_5") (pintype "passive"))
    )
    (net (code "39") (name "Net-(U4-DT)") (class "Default")
      (node (ref "C18") (pin "2") (pinfunction "2_2") (pintype "passive"))
      (node (ref "R24") (pin "2") (pinfunction "2_2") (pintype "passive"))
      (node (ref "U4") (pin "6") (pinfunction "DT_6") (pintype "passive"))
    )
    (net (code "40") (name "Net-(U4-INA)") (class "Default")
      (node (ref "C17") (pin "1") (pinfunction "1_1") (pintype "passive"))
      (node (ref "R20") (pin "1") (pinfunction "1_1") (pintype "passive"))
      (node (ref "R21") (pin "2") (pinfunction "2_2") (pintype "passive"))
      (node (ref "U4") (pin "1") (pinfunction "INA_1") (pintype "passive"))
    )
    (net (code "41") (name "Net-(U4-INB)") (class "Default")
      (node (ref "C16") (pin "1") (pinfunction "1_1") (pintype "passive"))
      (node (ref "R19") (pin "1") (pinfunction "1_1") (pintype "passive"))
      (node (ref "R22") (pin "2") (pinfunction "2_2") (pintype "passive"))
      (node (ref "U4") (pin "2") (pinfunction "INB_2") (pintype "passive"))
    )
    (net (code "42") (name "Net-(U4-OUTA)") (class "Default")
      (node (ref "D2") (pin "C") (pinfunction "C_C") (pintype "passive"))
      (node (ref "R17") (pin "1") (pinfunction "1_1") (pintype "passive"))
      (node (ref "U4") (pin "15") (pinfunction "OUTA_15") (pintype "passive"))
    )
    (net (code "43") (name "Net-(U4-OUTB)") (class "Default")
      (node (ref "D3") (pin "C") (pinfunction "C_C") (pintype "passive"))
      (node (ref "R58") (pin "2") (pinfunction "2_2") (pintype "passive"))
      (node (ref "U4") (pin "10") (pinfunction "OUTB_10") (pintype "passive"))
    )
    (net (code "44") (name "Net-(U5-DISABLE)") (class "Default")
      (node (ref "C25") (pin "1") (pinfunction "1_1") (pintype "passive"))
      (node (ref "R30") (pin "1") (pinfunction "1_1") (pintype "passive"))
      (node (ref "R62") (pin "2") (pinfunction "2_2") (pintype "passive"))
      (node (ref "U5") (pin "5") (pinfunction "DISABLE_5") (pintype "passive"))
    )
    (net (code "45") (name "Net-(U5-DT)") (class "Default")
      (node (ref "C95") (pin "2") (pinfunction "2_2") (pintype "passive"))
      (node (ref "R36") (pin "2") (pinfunction "2_2") (pintype "passive"))
      (node (ref "U5") (pin "6") (pinfunction "DT_6") (pintype "passive"))
    )
    (net (code "46") (name "Net-(U5-INA)") (class "Default")
      (node (ref "C83") (pin "1") (pinfunction "1_1") (pintype "passive"))
      (node (ref "R32") (pin "1") (pinfunction "1_1") (pintype "passive"))
      (node (ref "R61") (pin "2") (pinfunction "2_2") (pintype "passive"))
      (node (ref "U5") (pin "1") (pinfunction "INA_1") (pintype "passive"))
    )
    (net (code "47") (name "Net-(U5-INB)") (class "Default")
      (node (ref "C26") (pin "1") (pinfunction "1_1") (pintype "passive"))
      (node (ref "R31") (pin "1") (pinfunction "1_1") (pintype "passive"))
      (node (ref "R34") (pin "2") (pinfunction "2_2") (pintype "passive"))
      (node (ref "U5") (pin "2") (pinfunction "INB_2") (pintype "passive"))
    )
    (net (code "48") (name "Net-(U5-OUTA)") (class "Default")
      (node (ref "D5") (pin "C") (pinfunction "C_C") (pintype "passive"))
      (node (ref "R29") (pin "1") (pinfunction "1_1") (pintype "passive"))
      (node (ref "U5") (pin "15") (pinfunction "OUTA_15") (pintype "passive"))
    )
    (net (code "49") (name "Net-(U5-OUTB)") (class "Default")
      (node (ref "D6") (pin "C") (pinfunction "C_C") (pintype "passive"))
      (node (ref "R37") (pin "2") (pinfunction "2_2") (pintype "passive"))
      (node (ref "U5") (pin "10") (pinfunction "OUTB_10") (pintype "passive"))
    )
    (net (code "50") (name "Net-(U6-DISABLE)") (class "Default")
      (node (ref "C35") (pin "1") (pinfunction "1_1") (pintype "passive"))
      (node (ref "R42") (pin "1") (pinfunction "1_1") (pintype "passive"))
      (node (ref "R64") (pin "2") (pinfunction "2_2") (pintype "passive"))
      (node (ref "U6") (pin "5") (pinfunction "DISABLE_5") (pintype "passive"))
    )
    (net (code "51") (name "Net-(U6-DT)") (class "Default")
      (node (ref "C38") (pin "2") (pinfunction "2_2") (pintype "passive"))
      (node (ref "R48") (pin "2") (pinfunction "2_2") (pintype "passive"))
      (node (ref "U6") (pin "6") (pinfunction "DT_6") (pintype "passive"))
    )
    (net (code "52") (name "Net-(U6-INA)") (class "Default")
      (node (ref "C37") (pin "1") (pinfunction "1_1") (pintype "passive"))
      (node (ref "R44") (pin "1") (pinfunction "1_1") (pintype "passive"))
      (node (ref "R45") (pin "2") (pinfunction "2_2") (pintype "passive"))
      (node (ref "U6") (pin "1") (pinfunction "INA_1") (pintype "passive"))
    )
    (net (code "53") (name "Net-(U6-INB)") (class "Default")
      (node (ref "C36") (pin "1") (pinfunction "1_1") (pintype "passive"))
      (node (ref "R43") (pin "1") (pinfunction "1_1") (pintype "passive"))
      (node (ref "R63") (pin "2") (pinfunction "2_2") (pintype "passive"))
      (node (ref "U6") (pin "2") (pinfunction "INB_2") (pintype "passive"))
    )
    (net (code "54") (name "Net-(U6-OUTA)") (class "Default")
      (node (ref "D8") (pin "C") (pinfunction "C_C") (pintype "passive"))
      (node (ref "R41") (pin "1") (pinfunction "1_1") (pintype "passive"))
      (node (ref "U6") (pin "15") (pinfunction "OUTA_15") (pintype "passive"))
    )
    (net (code "55") (name "Net-(U6-OUTB)") (class "Default")
      (node (ref "D9") (pin "C") (pinfunction "C_C") (pintype "passive"))
      (node (ref "R65") (pin "2") (pinfunction "2_2") (pintype "passive"))
      (node (ref "U6") (pin "10") (pinfunction "OUTB_10") (pintype "passive"))
    )
    (net (code "56") (name "VIN+") (class "Default")
      (node (ref "J24") (pin "1") (pinfunction "1_1") (pintype "passive"))
      (node (ref "J24") (pin "10") (pinfunction "10_10") (pintype "passive"))
      (node (ref "J24") (pin "2") (pinfunction "2_2") (pintype "passive"))
      (node (ref "J24") (pin "3") (pinfunction "3_3") (pintype "passive"))
      (node (ref "J24") (pin "4") (pinfunction "4_4") (pintype "passive"))
      (node (ref "J24") (pin "5") (pinfunction "5_5") (pintype "passive"))
      (node (ref "J24") (pin "6") (pinfunction "6_6") (pintype "passive"))
      (node (ref "J24") (pin "7") (pinfunction "7_7") (pintype "passive"))
      (node (ref "J24") (pin "8") (pinfunction "8_8") (pintype "passive"))
      (node (ref "J24") (pin "9") (pinfunction "9_9") (pintype "passive"))
    )
    (net (code "57") (name "unconnected-(U4-NC_1-Pad7)") (class "Default")
      (node (ref "U4") (pin "7") (pinfunction "NC_1_7") (pintype "passive"))
    )
    (net (code "58") (name "unconnected-(U4-NC_2-Pad12)") (class "Default")
      (node (ref "U4") (pin "12") (pinfunction "NC_2_12") (pintype "passive"))
    )
    (net (code "59") (name "unconnected-(U4-NC_3-Pad13)") (class "Default")
      (node (ref "U4") (pin "13") (pinfunction "NC_3_13") (pintype "passive"))
    )
    (net (code "60") (name "unconnected-(U5-NC_1-Pad7)") (class "Default")
      (node (ref "U5") (pin "7") (pinfunction "NC_1_7") (pintype "passive"))
    )
    (net (code "61") (name "unconnected-(U5-NC_2-Pad12)") (class "Default")
      (node (ref "U5") (pin "12") (pinfunction "NC_2_12") (pintype "passive"))
    )
    (net (code "62") (name "unconnected-(U5-NC_3-Pad13)") (class "Default")
      (node (ref "U5") (pin "13") (pinfunction "NC_3_13") (pintype "passive"))
    )
    (net (code "63") (name "unconnected-(U6-NC_1-Pad7)") (class "Default")
      (node (ref "U6") (pin "7") (pinfunction "NC_1_7") (pintype "passive"))
    )
    (net (code "64") (name "unconnected-(U6-NC_2-Pad12)") (class "Default")
      (node (ref "U6") (pin "12") (pinfunction "NC_2_12") (pintype "passive"))
    )
    (net (code "65") (name "unconnected-(U6-NC_3-Pad13)") (class "Default")
      (node (ref "U6") (pin "13") (pinfunction "NC_3_13") (pintype "passive"))
    )
  )
)
